# Transmitter_Bug-2SC9014.net
KiCad netlist of a schematic drawn in EAGLE
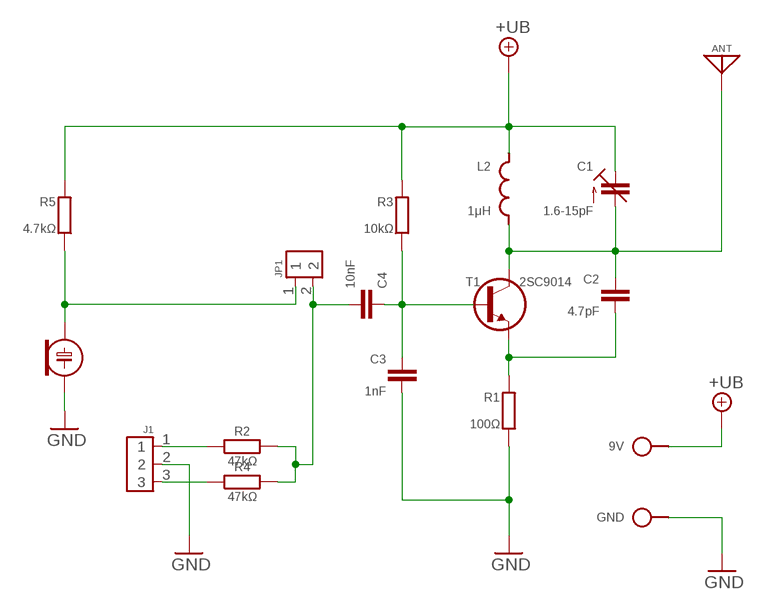
[diagram p0: schematic, sheet 1]

(export (version "E")
  (design (tool "Eeschema 10.0.6"))
  (components
    (comp (ref "9V")
      (value "SPAD")
      (footprint "eagle-import:SPAD")
      (libsource (lib "eagle-import") (part "SPAD"))
    )
    (comp (ref "ANT")
      (value "ANT")
      (footprint "eagle-import:SPAD")
      (libsource (lib "eagle-import") (part "ANT"))
    )
    (comp (ref "C1")
      (value "1.6-15pF")
      (footprint "eagle-import:TRIM-2222-808")
      (libsource (lib "eagle-import") (part "C-TR-PH201272222-808-2PINB"))
    )
    (comp (ref "C2")
      (value "4.7pF")
      (footprint "eagle-import:C025-015X024")
      (libsource (lib "eagle-import") (part "C025-015X024"))
    )
    (comp (ref "C3")
      (value "1nF")
      (footprint "eagle-import:C050-020X036_V")
      (libsource (lib "eagle-import") (part "C050-020X036/V"))
    )
    (comp (ref "C4")
      (value "10nF")
      (footprint "eagle-import:C050-020X036_V")
      (libsource (lib "eagle-import") (part "C050-020X036/V"))
    )
    (comp (ref "ECM1")
      (value "ECM-5")
      (footprint "eagle-import:ECM-5")
      (libsource (lib "eagle-import") (part "ECM-5"))
    )
    (comp (ref "GND")
      (value "SPAD")
      (footprint "eagle-import:SPAD")
      (libsource (lib "eagle-import") (part "SPAD"))
    )
    (comp (ref "J1")
      (value "CONN-3P-3P")
      (footprint "eagle-import:CONN-3P")
      (libsource (lib "eagle-import") (part "CONN-3P-3P"))
    )
    (comp (ref "JP1")
      (value "CONN-2P2P/V")
      (footprint "eagle-import:CONN-2P-V")
      (libsource (lib "eagle-import") (part "CONN-2P2P/V"))
    )
    (comp (ref "L2")
      (value "1μH")
      (footprint "eagle-import:L-04-2_5V-X")
      (libsource (lib "eagle-import") (part "L-SHORT04-5/5V-X"))
    )
    (comp (ref "R1")
      (value "100Ω")
      (footprint "eagle-import:0204_2V")
      (libsource (lib "eagle-import") (part "R0204/2V"))
    )
    (comp (ref "R2")
      (value "47kΩ")
      (footprint "eagle-import:0204_7-V")
      (libsource (lib "eagle-import") (part "R-H0204/7-V"))
    )
    (comp (ref "R3")
      (value "10kΩ")
      (footprint "eagle-import:0204_10-V")
      (libsource (lib "eagle-import") (part "R0204/10-V"))
    )
    (comp (ref "R4")
      (value "47kΩ")
      (footprint "eagle-import:0204_7-V")
      (libsource (lib "eagle-import") (part "R-H0204/7-V"))
    )
    (comp (ref "R5")
      (value "4.7kΩ")
      (footprint "eagle-import:0204_10-V")
      (libsource (lib "eagle-import") (part "R0204/10-V"))
    )
    (comp (ref "T1")
      (value "2SC9014")
      (footprint "eagle-import:TO92-EBC")
      (libsource (lib "eagle-import") (part "2SC9014"))
    )
  )
  (nets
    (net (code "1") (name "+UB") (class "Default")
      (node (ref "9V") (pin "1") (pinfunction "P$1_1") (pintype "bidirectional"))
      (node (ref "C1") (pin "3") (pinfunction "E_3") (pintype "passive"))
      (node (ref "L2") (pin "1") (pinfunction "2_1") (pintype "passive"))
      (node (ref "R3") (pin "1") (pinfunction "1_1") (pintype "passive"))
      (node (ref "R5") (pin "1") (pinfunction "1_1") (pintype "passive"))
    )
    (net (code "2") (name "GND") (class "Default")
      (node (ref "C3") (pin "2") (pinfunction "2_2") (pintype "passive"))
      (node (ref "ECM1") (pin "2") (pinfunction "-_2") (pintype "passive"))
      (node (ref "GND") (pin "1") (pinfunction "P$1_1") (pintype "bidirectional"))
      (node (ref "J1") (pin "2") (pinfunction "2_2") (pintype "bidirectional"))
      (node (ref "R1") (pin "1") (pinfunction "2_1") (pintype "passive"))
    )
    (net (code "3") (name "Net-(C1-A)") (class "Default")
      (node (ref "ANT") (pin "1") (pinfunction "1_1") (pintype "output"))
      (node (ref "C1") (pin "2") (pinfunction "A_2") (pintype "passive"))
      (node (ref "C2") (pin "1") (pinfunction "1_1") (pintype "passive"))
      (node (ref "L2") (pin "2") (pinfunction "1_2") (pintype "passive"))
      (node (ref "T1") (pin "C") (pinfunction "C_C") (pintype "passive"))
    )
    (net (code "4") (name "Net-(C3-Pad1)") (class "Default")
      (node (ref "C3") (pin "1") (pinfunction "1_1") (pintype "passive"))
      (node (ref "C4") (pin "1") (pinfunction "1_1") (pintype "passive"))
      (node (ref "R3") (pin "2") (pinfunction "2_2") (pintype "passive"))
      (node (ref "T1") (pin "B") (pinfunction "B_B") (pintype "passive"))
    )
    (net (code "5") (name "Net-(C4-Pad2)") (class "Default")
      (node (ref "C4") (pin "2") (pinfunction "2_2") (pintype "passive"))
      (node (ref "JP1") (pin "2") (pinfunction "2_2") (pintype "bidirectional"))
      (node (ref "R2") (pin "2") (pinfunction "2_2") (pintype "passive"))
      (node (ref "R4") (pin "2") (pinfunction "2_2") (pintype "passive"))
    )
    (net (code "6") (name "Net-(ECM1-+)") (class "Default")
      (node (ref "ECM1") (pin "1") (pinfunction "+_1") (pintype "passive"))
      (node (ref "JP1") (pin "1") (pinfunction "1_1") (pintype "bidirectional"))
      (node (ref "R5") (pin "2") (pinfunction "2_2") (pintype "passive"))
    )
    (net (code "7") (name "Net-(J1-Pad1)") (class "Default")
      (node (ref "J1") (pin "1") (pinfunction "1_1") (pintype "bidirectional"))
      (node (ref "R2") (pin "1") (pinfunction "1_1") (pintype "passive"))
    )
    (net (code "8") (name "Net-(J1-Pad3)") (class "Default")
      (node (ref "J1") (pin "3") (pinfunction "3_3") (pintype "bidirectional"))
      (node (ref "R4") (pin "1") (pinfunction "1_1") (pintype "passive"))
    )
    (net (code "9") (name "Net-(R1-1)") (class "Default")
      (node (ref "C2") (pin "2") (pinfunction "2_2") (pintype "passive"))
      (node (ref "R1") (pin "2") (pinfunction "1_2") (pintype "passive"))
      (node (ref "T1") (pin "E") (pinfunction "E_E") (pintype "passive"))
    )
  )
)
